# RodOfCommand.net
KiCad netlist of a schematic drawn in EAGLE
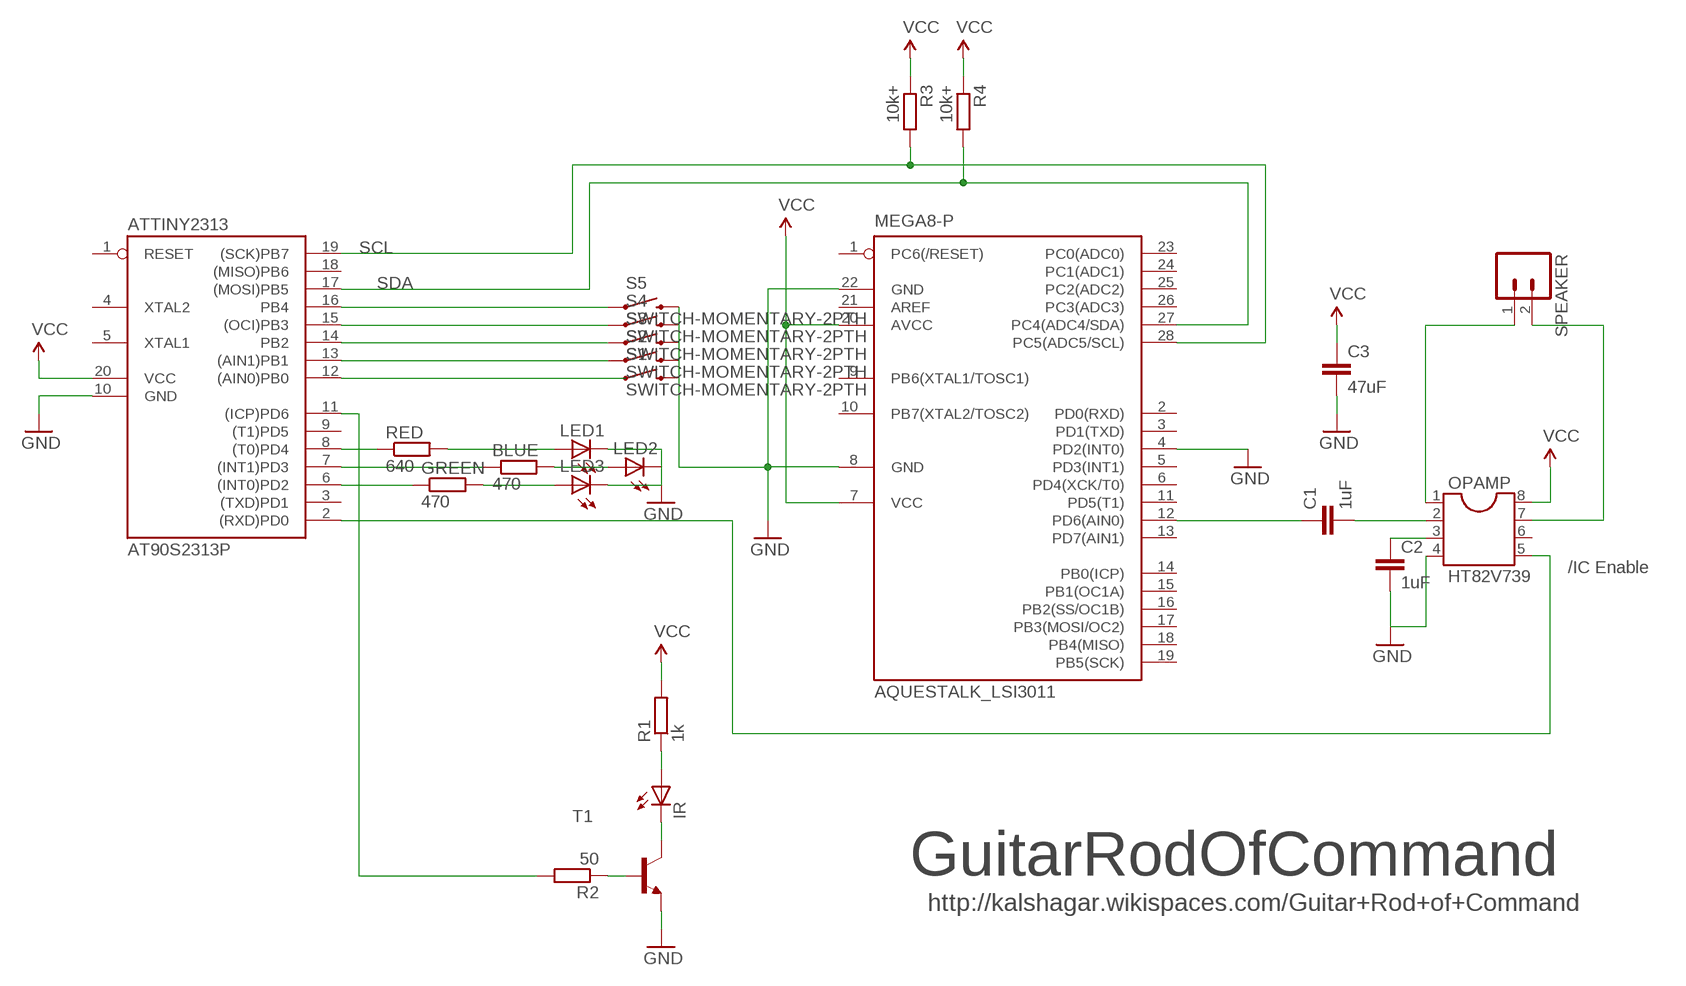
[diagram p0: schematic, sheet 1]

(export (version "E")
  (design (tool "Eeschema 10.0.6"))
  (components
    (comp (ref "AQUESTALK_LSI3011")
      (value "MEGA8-P")
      (footprint "eagle-import:DIL28-3")
      (libsource (lib "eagle-import") (part "MEGA8-P"))
    )
    (comp (ref "ATTINY2313")
      (value "AT90S2313P")
      (footprint "eagle-import:DIL20")
      (libsource (lib "eagle-import") (part "AT90S2313P"))
    )
    (comp (ref "BLUE")
      (value "470")
      (footprint "eagle-import:0204_5")
      (libsource (lib "eagle-import") (part "R-EU_0204/5"))
    )
    (comp (ref "C1")
      (value "1uF")
      (footprint "eagle-import:C025-024X044")
      (libsource (lib "eagle-import") (part "C-EU025-024X044"))
    )
    (comp (ref "C2")
      (value "1uF")
      (footprint "eagle-import:C025-024X044")
      (libsource (lib "eagle-import") (part "C-EU025-024X044"))
    )
    (comp (ref "C3")
      (value "47uF")
      (footprint "eagle-import:C025-024X044")
      (libsource (lib "eagle-import") (part "C-EU025-024X044"))
    )
    (comp (ref "GREEN")
      (value "470")
      (footprint "eagle-import:0204_5")
      (libsource (lib "eagle-import") (part "R-EU_0204/5"))
    )
    (comp (ref "IR")
      (value "LED5MM")
      (footprint "eagle-import:LED5MM")
      (libsource (lib "eagle-import") (part "LED5MM"))
    )
    (comp (ref "LED1")
      (value "LED-3MM-NO_SILK")
      (footprint "eagle-import:LED3MM-NS")
      (libsource (lib "eagle-import") (part "LED-3MM-NO_SILK"))
    )
    (comp (ref "LED2")
      (value "LED-3MM-NO_SILK")
      (footprint "eagle-import:LED3MM-NS")
      (libsource (lib "eagle-import") (part "LED-3MM-NO_SILK"))
    )
    (comp (ref "LED3")
      (value "LED-3MM-NO_SILK")
      (footprint "eagle-import:LED3MM-NS")
      (libsource (lib "eagle-import") (part "LED-3MM-NO_SILK"))
    )
    (comp (ref "OPAMP")
      (value "HT82V739")
      (footprint "eagle-import:DIL08")
      (libsource (lib "eagle-import") (part "DIL8"))
    )
    (comp (ref "R1")
      (value "1k")
      (footprint "eagle-import:0204_7")
      (libsource (lib "eagle-import") (part "R-EU_0204/7"))
    )
    (comp (ref "R2")
      (value "50")
      (footprint "eagle-import:0204_7")
      (libsource (lib "eagle-import") (part "R-EU_0204/7"))
    )
    (comp (ref "R3")
      (value "10k+")
      (footprint "eagle-import:0204_7")
      (libsource (lib "eagle-import") (part "R-EU_0204/7"))
    )
    (comp (ref "R4")
      (value "10k+")
      (footprint "eagle-import:0204_7")
      (libsource (lib "eagle-import") (part "R-EU_0204/7"))
    )
    (comp (ref "RED")
      (value "640")
      (footprint "eagle-import:0204_5")
      (libsource (lib "eagle-import") (part "R-EU_0204/5"))
    )
    (comp (ref "S1")
      (value "SWITCH-MOMENTARY-2PTH")
      (footprint "eagle-import:TACTILE-PTH")
      (libsource (lib "eagle-import") (part "SWITCH-MOMENTARY-2PTH"))
    )
    (comp (ref "S2")
      (value "SWITCH-MOMENTARY-2PTH")
      (footprint "eagle-import:TACTILE-PTH")
      (libsource (lib "eagle-import") (part "SWITCH-MOMENTARY-2PTH"))
    )
    (comp (ref "S3")
      (value "SWITCH-MOMENTARY-2PTH")
      (footprint "eagle-import:TACTILE-PTH")
      (libsource (lib "eagle-import") (part "SWITCH-MOMENTARY-2PTH"))
    )
    (comp (ref "S4")
      (value "SWITCH-MOMENTARY-2PTH")
      (footprint "eagle-import:TACTILE-PTH")
      (libsource (lib "eagle-import") (part "SWITCH-MOMENTARY-2PTH"))
    )
    (comp (ref "S5")
      (value "SWITCH-MOMENTARY-2PTH")
      (footprint "eagle-import:TACTILE-PTH")
      (libsource (lib "eagle-import") (part "SWITCH-MOMENTARY-2PTH"))
    )
    (comp (ref "SPEAKER")
      (value "M02LOCK")
      (footprint "eagle-import:1X02_LOCK")
      (libsource (lib "eagle-import") (part "M02LOCK"))
    )
    (comp (ref "T1")
      (value "-NPN-TO92-ECB")
      (footprint "eagle-import:TO92-ECB")
      (libsource (lib "eagle-import") (part "-NPN-TO92-ECB"))
    )
  )
  (nets
    (net (code "1") (name "GND") (class "Default")
      (node (ref "AQUESTALK_LSI3011") (pin "22") (pinfunction "GND_22") (pintype "power_in"))
      (node (ref "AQUESTALK_LSI3011") (pin "4") (pinfunction "PD2(INT0)_4") (pintype "bidirectional"))
      (node (ref "AQUESTALK_LSI3011") (pin "8") (pinfunction "GND_8") (pintype "power_in"))
      (node (ref "ATTINY2313") (pin "10") (pinfunction "GND_10") (pintype "power_in"))
      (node (ref "C2") (pin "2") (pinfunction "2_2") (pintype "passive"))
      (node (ref "C3") (pin "2") (pinfunction "2_2") (pintype "passive"))
      (node (ref "LED1") (pin "K") (pinfunction "C_K") (pintype "passive"))
      (node (ref "LED2") (pin "K") (pinfunction "C_K") (pintype "passive"))
      (node (ref "LED3") (pin "K") (pinfunction "C_K") (pintype "passive"))
      (node (ref "OPAMP") (pin "4") (pinfunction "4_4") (pintype "passive"))
      (node (ref "S1") (pin "3") (pinfunction "2_3") (pintype "passive"))
      (node (ref "S2") (pin "3") (pinfunction "2_3") (pintype "passive"))
      (node (ref "S3") (pin "3") (pinfunction "2_3") (pintype "passive"))
      (node (ref "S4") (pin "3") (pinfunction "2_3") (pintype "passive"))
      (node (ref "S5") (pin "3") (pinfunction "2_3") (pintype "passive"))
      (node (ref "T1") (pin "E") (pinfunction "E_E") (pintype "passive"))
    )
    (net (code "2") (name "Net-(AQUESTALK_LSI3011-PC4(ADC4{slash}SDA))") (class "Default")
      (node (ref "AQUESTALK_LSI3011") (pin "27") (pinfunction "PC4(ADC4/SDA)_27") (pintype "bidirectional"))
      (node (ref "ATTINY2313") (pin "17") (pinfunction "(MOSI)PB5_17") (pintype "bidirectional"))
      (node (ref "R4") (pin "2") (pinfunction "2_2") (pintype "passive"))
    )
    (net (code "3") (name "Net-(AQUESTALK_LSI3011-PC5(ADC5{slash}SCL))") (class "Default")
      (node (ref "AQUESTALK_LSI3011") (pin "28") (pinfunction "PC5(ADC5/SCL)_28") (pintype "bidirectional"))
      (node (ref "ATTINY2313") (pin "19") (pinfunction "(SCK)PB7_19") (pintype "bidirectional"))
      (node (ref "R3") (pin "2") (pinfunction "2_2") (pintype "passive"))
    )
    (net (code "4") (name "Net-(AQUESTALK_LSI3011-PD6(AIN0))") (class "Default")
      (node (ref "AQUESTALK_LSI3011") (pin "12") (pinfunction "PD6(AIN0)_12") (pintype "bidirectional"))
      (node (ref "C1") (pin "1") (pinfunction "1_1") (pintype "passive"))
    )
    (net (code "5") (name "Net-(ATTINY2313-(AIN1)PB1)") (class "Default")
      (node (ref "ATTINY2313") (pin "13") (pinfunction "(AIN1)PB1_13") (pintype "bidirectional"))
      (node (ref "S2") (pin "1") (pinfunction "1_1") (pintype "passive"))
    )
    (net (code "6") (name "Net-(ATTINY2313-(ICP)PD6)") (class "Default")
      (node (ref "ATTINY2313") (pin "11") (pinfunction "(ICP)PD6_11") (pintype "bidirectional"))
      (node (ref "R2") (pin "2") (pinfunction "2_2") (pintype "passive"))
    )
    (net (code "7") (name "Net-(ATTINY2313-(INT0)PD2)") (class "Default")
      (node (ref "ATTINY2313") (pin "6") (pinfunction "(INT0)PD2_6") (pintype "bidirectional"))
      (node (ref "GREEN") (pin "1") (pinfunction "1_1") (pintype "passive"))
    )
    (net (code "8") (name "Net-(ATTINY2313-(INT1)PD3)") (class "Default")
      (node (ref "ATTINY2313") (pin "7") (pinfunction "(INT1)PD3_7") (pintype "bidirectional"))
      (node (ref "BLUE") (pin "1") (pinfunction "1_1") (pintype "passive"))
    )
    (net (code "9") (name "Net-(ATTINY2313-(OCI)PB3)") (class "Default")
      (node (ref "ATTINY2313") (pin "15") (pinfunction "(OCI)PB3_15") (pintype "bidirectional"))
      (node (ref "S4") (pin "1") (pinfunction "1_1") (pintype "passive"))
    )
    (net (code "10") (name "Net-(ATTINY2313-(RXD)PD0)") (class "Default")
      (node (ref "ATTINY2313") (pin "2") (pinfunction "(RXD)PD0_2") (pintype "bidirectional"))
      (node (ref "OPAMP") (pin "5") (pinfunction "5_5") (pintype "passive"))
    )
    (net (code "11") (name "Net-(ATTINY2313-(T0)PD4)") (class "Default")
      (node (ref "ATTINY2313") (pin "8") (pinfunction "(T0)PD4_8") (pintype "bidirectional"))
      (node (ref "RED") (pin "1") (pinfunction "1_1") (pintype "passive"))
    )
    (net (code "12") (name "Net-(ATTINY2313-PB2)") (class "Default")
      (node (ref "ATTINY2313") (pin "14") (pinfunction "PB2_14") (pintype "bidirectional"))
      (node (ref "S3") (pin "1") (pinfunction "1_1") (pintype "passive"))
    )
    (net (code "13") (name "Net-(ATTINY2313-PB4)") (class "Default")
      (node (ref "ATTINY2313") (pin "16") (pinfunction "PB4_16") (pintype "bidirectional"))
      (node (ref "S5") (pin "1") (pinfunction "1_1") (pintype "passive"))
    )
    (net (code "14") (name "Net-(BLUE-Pad2)") (class "Default")
      (node (ref "BLUE") (pin "2") (pinfunction "2_2") (pintype "passive"))
      (node (ref "LED2") (pin "A") (pinfunction "A_A") (pintype "passive"))
    )
    (net (code "15") (name "Net-(C1-Pad2)") (class "Default")
      (node (ref "C1") (pin "2") (pinfunction "2_2") (pintype "passive"))
      (node (ref "OPAMP") (pin "2") (pinfunction "2_2") (pintype "passive"))
    )
    (net (code "16") (name "Net-(C2-Pad1)") (class "Default")
      (node (ref "C2") (pin "1") (pinfunction "1_1") (pintype "passive"))
      (node (ref "OPAMP") (pin "3") (pinfunction "3_3") (pintype "passive"))
    )
    (net (code "17") (name "Net-(GREEN-Pad2)") (class "Default")
      (node (ref "GREEN") (pin "2") (pinfunction "2_2") (pintype "passive"))
      (node (ref "LED3") (pin "A") (pinfunction "A_A") (pintype "passive"))
    )
    (net (code "18") (name "Net-(IR-C)") (class "Default")
      (node (ref "IR") (pin "K") (pinfunction "C_K") (pintype "passive"))
      (node (ref "T1") (pin "C") (pinfunction "C_C") (pintype "passive"))
    )
    (net (code "19") (name "Net-(IR-PadA)") (class "Default")
      (node (ref "IR") (pin "A") (pinfunction "A_A") (pintype "passive"))
      (node (ref "R1") (pin "1") (pinfunction "1_1") (pintype "passive"))
    )
    (net (code "20") (name "Net-(LED1-PadA)") (class "Default")
      (node (ref "LED1") (pin "A") (pinfunction "A_A") (pintype "passive"))
      (node (ref "RED") (pin "2") (pinfunction "2_2") (pintype "passive"))
    )
    (net (code "21") (name "Net-(OPAMP-Pad1)") (class "Default")
      (node (ref "OPAMP") (pin "1") (pinfunction "1_1") (pintype "passive"))
      (node (ref "SPEAKER") (pin "1") (pinfunction "1_1") (pintype "passive"))
    )
    (net (code "22") (name "Net-(OPAMP-Pad7)") (class "Default")
      (node (ref "OPAMP") (pin "7") (pinfunction "7_7") (pintype "passive"))
      (node (ref "SPEAKER") (pin "2") (pinfunction "2_2") (pintype "passive"))
    )
    (net (code "23") (name "Net-(R2-Pad1)") (class "Default")
      (node (ref "R2") (pin "1") (pinfunction "1_1") (pintype "passive"))
      (node (ref "T1") (pin "B") (pinfunction "B_B") (pintype "passive"))
    )
    (net (code "24") (name "VCC") (class "Default")
      (node (ref "AQUESTALK_LSI3011") (pin "20") (pinfunction "AVCC_20") (pintype "power_in"))
      (node (ref "AQUESTALK_LSI3011") (pin "7") (pinfunction "VCC_7") (pintype "power_in"))
      (node (ref "ATTINY2313") (pin "20") (pinfunction "VCC_20") (pintype "power_in"))
      (node (ref "C3") (pin "1") (pinfunction "1_1") (pintype "passive"))
      (node (ref "OPAMP") (pin "8") (pinfunction "8_8") (pintype "passive"))
      (node (ref "R1") (pin "2") (pinfunction "2_2") (pintype "passive"))
      (node (ref "R3") (pin "1") (pinfunction "1_1") (pintype "passive"))
      (node (ref "R4") (pin "1") (pinfunction "1_1") (pintype "passive"))
    )
    (net (code "25") (name "unconnected-(AQUESTALK_LSI3011-AREF-Pad21)") (class "Default")
      (node (ref "AQUESTALK_LSI3011") (pin "21") (pinfunction "AREF_21") (pintype "passive"))
    )
    (net (code "26") (name "unconnected-(AQUESTALK_LSI3011-PB0(ICP)-Pad14)") (class "Default")
      (node (ref "AQUESTALK_LSI3011") (pin "14") (pinfunction "PB0(ICP)_14") (pintype "bidirectional"))
    )
    (net (code "27") (name "unconnected-(AQUESTALK_LSI3011-PB1(OC1A)-Pad15)") (class "Default")
      (node (ref "AQUESTALK_LSI3011") (pin "15") (pinfunction "PB1(OC1A)_15") (pintype "bidirectional"))
    )
    (net (code "28") (name "unconnected-(AQUESTALK_LSI3011-PB2(SS{slash}OC1B)-Pad16)") (class "Default")
      (node (ref "AQUESTALK_LSI3011") (pin "16") (pinfunction "PB2(SS/OC1B)_16") (pintype "bidirectional"))
    )
    (net (code "29") (name "unconnected-(AQUESTALK_LSI3011-PB3(MOSI{slash}OC2)-Pad17)") (class "Default")
      (node (ref "AQUESTALK_LSI3011") (pin "17") (pinfunction "PB3(MOSI/OC2)_17") (pintype "bidirectional"))
    )
    (net (code "30") (name "unconnected-(AQUESTALK_LSI3011-PB4(MISO)-Pad18)") (class "Default")
      (node (ref "AQUESTALK_LSI3011") (pin "18") (pinfunction "PB4(MISO)_18") (pintype "bidirectional"))
    )
    (net (code "31") (name "unconnected-(AQUESTALK_LSI3011-PB5(SCK)-Pad19)") (class "Default")
      (node (ref "AQUESTALK_LSI3011") (pin "19") (pinfunction "PB5(SCK)_19") (pintype "bidirectional"))
    )
    (net (code "32") (name "unconnected-(AQUESTALK_LSI3011-PB6(XTAL1{slash}TOSC1)-Pad9)") (class "Default")
      (node (ref "AQUESTALK_LSI3011") (pin "9") (pinfunction "PB6(XTAL1/TOSC1)_9") (pintype "bidirectional"))
    )
    (net (code "33") (name "unconnected-(AQUESTALK_LSI3011-PB7(XTAL2{slash}TOSC2)-Pad10)") (class "Default")
      (node (ref "AQUESTALK_LSI3011") (pin "10") (pinfunction "PB7(XTAL2/TOSC2)_10") (pintype "bidirectional"))
    )
    (net (code "34") (name "unconnected-(AQUESTALK_LSI3011-PC0(ADC0)-Pad23)") (class "Default")
      (node (ref "AQUESTALK_LSI3011") (pin "23") (pinfunction "PC0(ADC0)_23") (pintype "bidirectional"))
    )
    (net (code "35") (name "unconnected-(AQUESTALK_LSI3011-PC1(ADC1)-Pad24)") (class "Default")
      (node (ref "AQUESTALK_LSI3011") (pin "24") (pinfunction "PC1(ADC1)_24") (pintype "bidirectional"))
    )
    (net (code "36") (name "unconnected-(AQUESTALK_LSI3011-PC2(ADC2)-Pad25)") (class "Default")
      (node (ref "AQUESTALK_LSI3011") (pin "25") (pinfunction "PC2(ADC2)_25") (pintype "bidirectional"))
    )
    (net (code "37") (name "unconnected-(AQUESTALK_LSI3011-PC3(ADC3)-Pad26)") (class "Default")
      (node (ref "AQUESTALK_LSI3011") (pin "26") (pinfunction "PC3(ADC3)_26") (pintype "bidirectional"))
    )
    (net (code "38") (name "unconnected-(AQUESTALK_LSI3011-PC6({slash}RESET)-Pad1)") (class "Default")
      (node (ref "AQUESTALK_LSI3011") (pin "1") (pinfunction "PC6(/RESET)_1") (pintype "bidirectional"))
    )
    (net (code "39") (name "unconnected-(AQUESTALK_LSI3011-PD0(RXD)-Pad2)") (class "Default")
      (node (ref "AQUESTALK_LSI3011") (pin "2") (pinfunction "PD0(RXD)_2") (pintype "bidirectional"))
    )
    (net (code "40") (name "unconnected-(AQUESTALK_LSI3011-PD1(TXD)-Pad3)") (class "Default")
      (node (ref "AQUESTALK_LSI3011") (pin "3") (pinfunction "PD1(TXD)_3") (pintype "bidirectional"))
    )
    (net (code "41") (name "unconnected-(AQUESTALK_LSI3011-PD3(INT1)-Pad5)") (class "Default")
      (node (ref "AQUESTALK_LSI3011") (pin "5") (pinfunction "PD3(INT1)_5") (pintype "bidirectional"))
    )
    (net (code "42") (name "unconnected-(AQUESTALK_LSI3011-PD4(XCK{slash}T0)-Pad6)") (class "Default")
      (node (ref "AQUESTALK_LSI3011") (pin "6") (pinfunction "PD4(XCK/T0)_6") (pintype "bidirectional"))
    )
    (net (code "43") (name "unconnected-(AQUESTALK_LSI3011-PD5(T1)-Pad11)") (class "Default")
      (node (ref "AQUESTALK_LSI3011") (pin "11") (pinfunction "PD5(T1)_11") (pintype "bidirectional"))
    )
    (net (code "44") (name "unconnected-(AQUESTALK_LSI3011-PD7(AIN1)-Pad13)") (class "Default")
      (node (ref "AQUESTALK_LSI3011") (pin "13") (pinfunction "PD7(AIN1)_13") (pintype "bidirectional"))
    )
    (net (code "45") (name "unconnected-(ATTINY2313-(AIN0)PB0-Pad12)") (class "Default")
      (node (ref "ATTINY2313") (pin "12") (pinfunction "(AIN0)PB0_12") (pintype "bidirectional"))
    )
    (net (code "46") (name "unconnected-(ATTINY2313-(MISO)PB6-Pad18)") (class "Default")
      (node (ref "ATTINY2313") (pin "18") (pinfunction "(MISO)PB6_18") (pintype "bidirectional"))
    )
    (net (code "47") (name "unconnected-(ATTINY2313-(T1)PD5-Pad9)") (class "Default")
      (node (ref "ATTINY2313") (pin "9") (pinfunction "(T1)PD5_9") (pintype "bidirectional"))
    )
    (net (code "48") (name "unconnected-(ATTINY2313-(TXD)PD1-Pad3)") (class "Default")
      (node (ref "ATTINY2313") (pin "3") (pinfunction "(TXD)PD1_3") (pintype "bidirectional"))
    )
    (net (code "49") (name "unconnected-(ATTINY2313-RESET-Pad1)") (class "Default")
      (node (ref "ATTINY2313") (pin "1") (pinfunction "RESET_1") (pintype "bidirectional"))
    )
    (net (code "50") (name "unconnected-(ATTINY2313-XTAL1-Pad5)") (class "Default")
      (node (ref "ATTINY2313") (pin "5") (pinfunction "XTAL1_5") (pintype "bidirectional"))
    )
    (net (code "51") (name "unconnected-(ATTINY2313-XTAL2-Pad4)") (class "Default")
      (node (ref "ATTINY2313") (pin "4") (pinfunction "XTAL2_4") (pintype "bidirectional"))
    )
    (net (code "52") (name "unconnected-(OPAMP-Pad6)") (class "Default")
      (node (ref "OPAMP") (pin "6") (pinfunction "6_6") (pintype "passive"))
    )
    (net (code "53") (name "unconnected-(S1-Pad1)") (class "Default")
      (node (ref "S1") (pin "1") (pinfunction "1_1") (pintype "passive"))
    )
  )
)
